# Device.net
KiCad netlist of a schematic drawn in Altium Designer
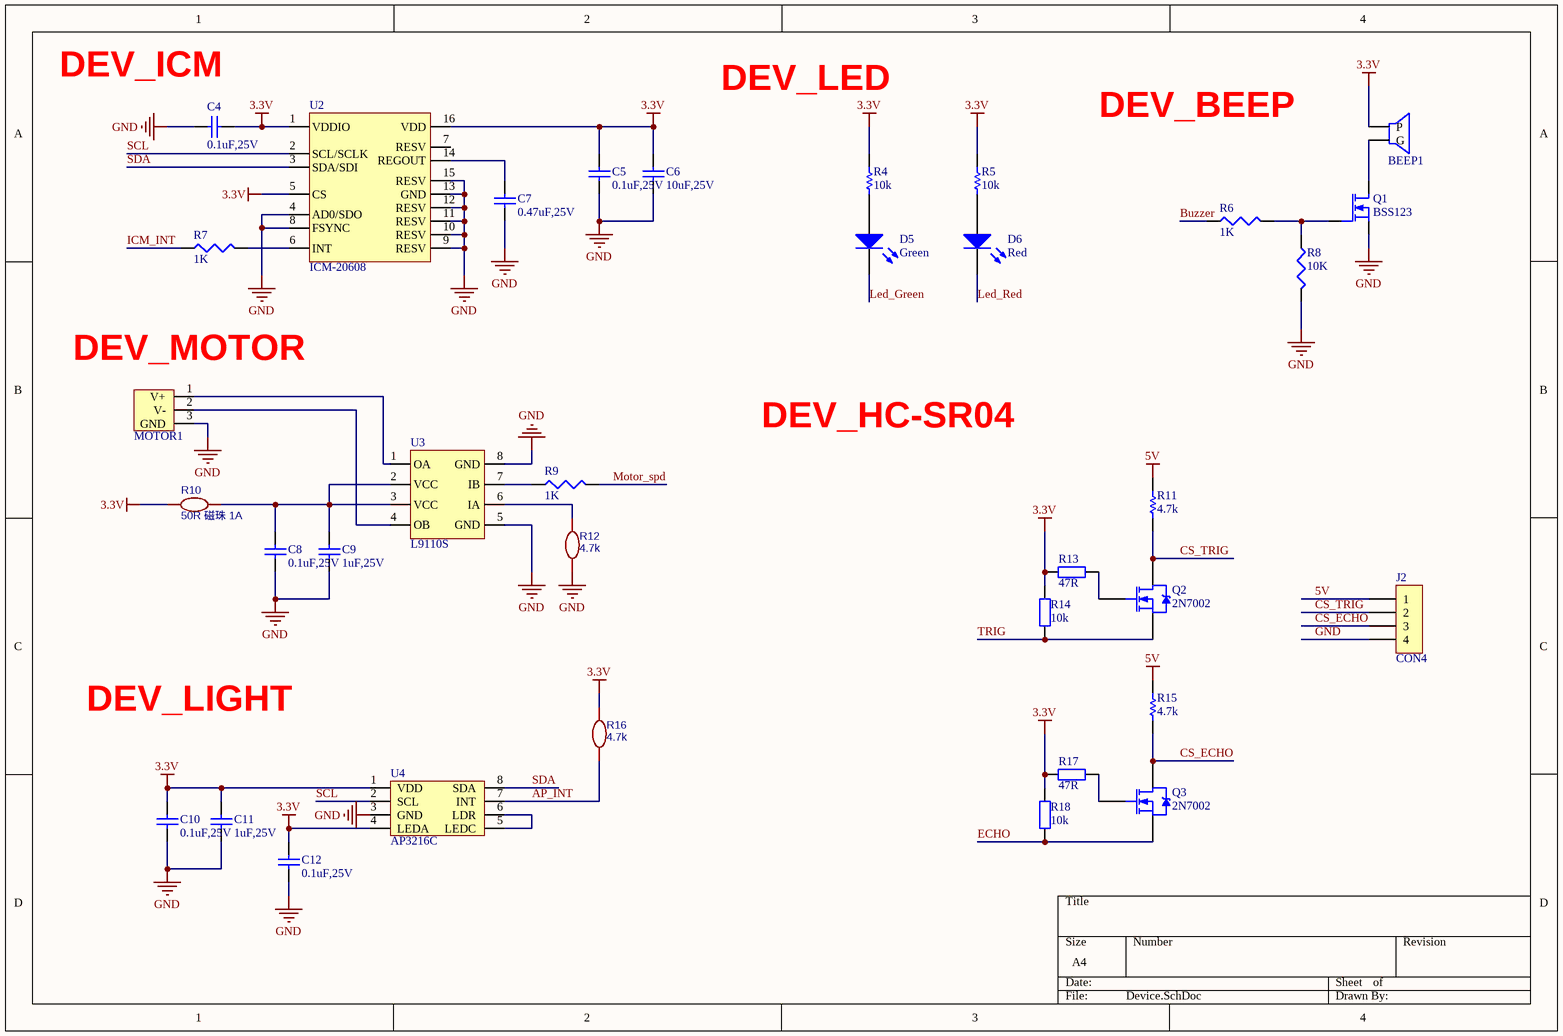
[diagram p0: Device.SchDoc]

(export (version "E")
  (design (tool "Eeschema 10.0.6"))
  (components
    (comp (ref "BEEP1")
      (value "BEEP")
      (footprint "BEEP")
      (description "3.3V有源蜂鸣器")
      (libsource (lib "Pandora_STM32L4_Board_V2.4") (part "BEEP"))
    )
    (comp (ref "C4")
      (value "0.1uF,25V")
      (footprint "0402_C")
      (description "贴片电容")
      (fields (field (name "PART NUMBER") "T_Cap_0603_0.1uF_25V_X5R") (field (name "TOLERANCE") "10%"))
      (libsource (lib "Database_Library") (part "Cap"))
    )
    (comp (ref "C5")
      (value "0.1uF,25V")
      (footprint "0402_C")
      (description "贴片电容")
      (fields (field (name "PART NUMBER") "T_Cap_0603_0.1uF_25V_X5R") (field (name "TOLERANCE") "10%"))
      (libsource (lib "Database_Library") (part "Cap"))
    )
    (comp (ref "C6")
      (value "10uF,25V")
      (footprint "0402_C")
      (description "贴片电容")
      (fields (field (name "PART NUMBER") "T_Cap_0603_0.1uF_25V_X5R") (field (name "TOLERANCE") "10%"))
      (libsource (lib "Database_Library") (part "Cap"))
    )
    (comp (ref "C7")
      (value "0.47uF,25V")
      (footprint "0402_C")
      (description "贴片电容")
      (fields (field (name "PART NUMBER") "T_Cap_0603_0.1uF_25V_X5R") (field (name "TOLERANCE") "10%"))
      (libsource (lib "Database_Library") (part "Cap"))
    )
    (comp (ref "C8")
      (value "0.1uF,25V")
      (footprint "0402_C")
      (description "贴片电容")
      (fields (field (name "PART NUMBER") "T_Cap_0603_0.1uF_25V_X5R") (field (name "TOLERANCE") "10%"))
      (libsource (lib "Database_Library") (part "Cap"))
    )
    (comp (ref "C9")
      (value "1uF,25V")
      (footprint "0402_C")
      (description "贴片电容")
      (fields (field (name "PART NUMBER") "T_Cap_0603_0.1uF_25V_X5R") (field (name "TOLERANCE") "10%"))
      (libsource (lib "Database_Library") (part "Cap"))
    )
    (comp (ref "C10")
      (value "0.1uF,25V")
      (footprint "0402_C")
      (description "贴片电容")
      (fields (field (name "PART NUMBER") "T_Cap_0603_0.1uF_25V_X5R") (field (name "TOLERANCE") "10%"))
      (libsource (lib "Database_Library") (part "Cap"))
    )
    (comp (ref "C11")
      (value "1uF,25V")
      (footprint "0402_C")
      (description "贴片电容")
      (fields (field (name "PART NUMBER") "T_Cap_0603_0.1uF_25V_X5R") (field (name "TOLERANCE") "10%"))
      (libsource (lib "Database_Library") (part "Cap"))
    )
    (comp (ref "C12")
      (value "0.1uF,25V")
      (footprint "0402_C")
      (description "贴片电容")
      (fields (field (name "PART NUMBER") "T_Cap_0603_0.1uF_25V_X5R") (field (name "TOLERANCE") "10%"))
      (libsource (lib "Database_Library") (part "Cap"))
    )
    (comp (ref "D5")
      (value "Green")
      (footprint "0603_LED")
      (description "红色LED灯")
      (fields (field (name "PART NUMBER") "T_LED_Red_0805"))
      (libsource (lib "Database_Library") (part "LED"))
    )
    (comp (ref "D6")
      (value "Red")
      (footprint "0603_LED")
      (description "红色LED灯")
      (fields (field (name "PART NUMBER") "T_LED_Red_0805"))
      (libsource (lib "Database_Library") (part "LED"))
    )
    (comp (ref "J2") (value "CON4") (description "Connector") (libsource (lib "Schlib1") (part "CON4")))
    (comp (ref "MOTOR1")
      (value "Motor-SMD")
      (footprint "MOTOR-SMD")
      (description "电机,SMD")
      (libsource (lib "Pandora_STM32L4_Board_V2.4") (part "Motor-SMD"))
    )
    (comp (ref "Q1")
      (value "BSS123")
      (footprint "SOT-23")
      (description "Mosfet, N-channel, Vds:100V, Id:0.15A, Vgs-th:2.8V, Rds-on:3.5ohm")
      (libsource (lib "HardWare_OF_BMS_V1.0") (part "BSS123"))
    )
    (comp (ref "Q2")
      (value "2N7002")
      (footprint "SOT-23!!!")
      (fields (field (name "PART NUMBER") "T_2N7002"))
      (libsource (lib "Database_Library") (part "NMOS"))
    )
    (comp (ref "Q3")
      (value "2N7002")
      (footprint "SOT-23!!!")
      (fields (field (name "PART NUMBER") "T_2N7002"))
      (libsource (lib "Database_Library") (part "NMOS"))
    )
    (comp (ref "R4")
      (value "10k")
      (footprint "0603_R")
      (description "贴片电阻")
      (fields (field (name "PART NUMBER") "T_Res_0603_10k_5%_1/10W") (field (name "POWER") "1/10W"))
      (libsource (lib "Database_Library") (part "Res_5%"))
    )
    (comp (ref "R5")
      (value "10k")
      (footprint "0603_R")
      (description "贴片电阻")
      (fields (field (name "PART NUMBER") "T_Res_0603_10k_5%_1/10W") (field (name "POWER") "1/10W"))
      (libsource (lib "Database_Library") (part "Res_5%"))
    )
    (comp (ref "R6")
      (value "1K")
      (footprint "0603_R")
      (description "Resistor, 1.5k, 0.1%, 0.0625W, 50V, 100PPM, 0402")
      (libsource (lib "AR_Resistors_SMD") (part "1.5k/0402/0063W/50V"))
    )
    (comp (ref "R7")
      (value "1K")
      (footprint "0603_R")
      (description "Resistor, 1.5k, 0.1%, 0.0625W, 50V, 100PPM, 0402")
      (libsource (lib "AR_Resistors_SMD") (part "1.5k/0402/0063W/50V"))
    )
    (comp (ref "R8")
      (value "10K")
      (footprint "0603_R")
      (description "Resistor, 1.5k, 0.1%, 0.0625W, 50V, 100PPM, 0402")
      (libsource (lib "AR_Resistors_SMD") (part "1.5k/0402/0063W/50V"))
    )
    (comp (ref "R9")
      (value "1K")
      (footprint "0603_R")
      (description "Resistor, 1.5k, 0.1%, 0.0625W, 50V, 100PPM, 0402")
      (libsource (lib "AR_Resistors_SMD") (part "1.5k/0402/0063W/50V"))
    )
    (comp (ref "R10")
      (value "50R 磁珠 1A")
      (footprint "0402_R")
      (fields (field (name "CONTRIBUTOR") "LCEDA_Lib"))
      (libsource (lib "altium-import") (part "root_2_100k_"))
    )
    (comp (ref "R11")
      (value "4.7k")
      (footprint "0603_R")
      (description "贴片电阻")
      (fields (field (name "PART NUMBER") "T_Res_0603_4.3k_5%_1/10W") (field (name "POWER") "1/10W"))
      (libsource (lib "Database_Library") (part "Res_5%"))
    )
    (comp (ref "R12")
      (value "4.7k")
      (footprint "0402_R")
      (fields (field (name "CONTRIBUTOR") "LCEDA_Lib"))
      (libsource (lib "altium-import") (part "root_3_100k_"))
    )
    (comp (ref "R13") (value "47R") (footprint "0603_R") (libsource (lib "MyLibrary") (part "Res")))
    (comp (ref "R14")
      (value "10k")
      (footprint "0603_R")
      (description "贴片电阻")
      (fields (field (name "PART NUMBER") "T_Res_0603_10k_1%_1/10W") (field (name "POWER") "1/10W"))
      (libsource (lib "Database_Library") (part "Res"))
    )
    (comp (ref "R15")
      (value "4.7k")
      (footprint "0603_R")
      (description "贴片电阻")
      (fields (field (name "PART NUMBER") "T_Res_0603_4.3k_5%_1/10W") (field (name "POWER") "1/10W"))
      (libsource (lib "Database_Library") (part "Res_5%"))
    )
    (comp (ref "R16")
      (value "4.7k")
      (footprint "0402_R")
      (fields (field (name "CONTRIBUTOR") "LCEDA_Lib"))
      (libsource (lib "altium-import") (part "root_3_100k_"))
    )
    (comp (ref "R17") (value "47R") (footprint "0603_R") (libsource (lib "MyLibrary") (part "Res")))
    (comp (ref "R18")
      (value "10k")
      (footprint "0603_R")
      (description "贴片电阻")
      (fields (field (name "PART NUMBER") "T_Res_0603_10k_1%_1/10W") (field (name "POWER") "1/10W"))
      (libsource (lib "Database_Library") (part "Res"))
    )
    (comp (ref "U2")
      (value "ICM-20608")
      (footprint "LGA-16-3*3*0.75")
      (description "三轴陀螺仪/三轴加速度计,")
      (libsource (lib "Pandora_STM32L4_Board_V2.4") (part "U-ICM-20608"))
    )
    (comp (ref "U3")
      (value "L9110S")
      (footprint "SOP-8")
      (description "电机驱动,800mA")
      (libsource (lib "Pandora_STM32L4_Board_V2.4") (part "U-L9110S"))
    )
    (comp (ref "U4")
      (value "AP3216C")
      (footprint "QFN-8-2.4*4.1")
      (description "Sensor.光照/距离")
      (libsource (lib "Pandora_STM32L4_Board_V2.4") (part "U-AP3216C"))
    )
  )
  (nets
    (net (code "1") (name "/AP_INT") (class "Default")
      (node (ref "R16") (pin "2") (pinfunction "2_2") (pintype "passive"))
      (node (ref "U4") (pin "7") (pinfunction "INT_7") (pintype "passive"))
    )
    (net (code "2") (name "/Buzzer") (class "Default")
      (node (ref "R6") (pin "1") (pinfunction "1_1") (pintype "passive"))
    )
    (net (code "3") (name "/CS_ECHO") (class "Default")
      (node (ref "J2") (pin "3") (pinfunction "3_3") (pintype "passive"))
      (node (ref "Q3") (pin "2") (pinfunction "D_2") (pintype "passive"))
      (node (ref "R15") (pin "1") (pinfunction "1_1") (pintype "passive"))
    )
    (net (code "4") (name "/CS_TRIG") (class "Default")
      (node (ref "J2") (pin "2") (pinfunction "2_2") (pintype "passive"))
      (node (ref "Q2") (pin "2") (pinfunction "D_2") (pintype "passive"))
      (node (ref "R11") (pin "1") (pinfunction "1_1") (pintype "passive"))
    )
    (net (code "5") (name "/ECHO") (class "Default")
      (node (ref "Q3") (pin "3") (pinfunction "S_3") (pintype "passive"))
      (node (ref "R18") (pin "1") (pinfunction "1_1") (pintype "passive"))
    )
    (net (code "6") (name "/ICM_INT") (class "Default")
      (node (ref "R7") (pin "1") (pinfunction "1_1") (pintype "passive"))
    )
    (net (code "7") (name "/Led_Green") (class "Default")
      (node (ref "D5") (pin "2") (pinfunction "K_2") (pintype "passive"))
    )
    (net (code "8") (name "/Led_Red") (class "Default")
      (node (ref "D6") (pin "2") (pinfunction "K_2") (pintype "passive"))
    )
    (net (code "9") (name "/Motor_spd") (class "Default")
      (node (ref "R9") (pin "2") (pinfunction "2_2") (pintype "passive"))
    )
    (net (code "10") (name "/SCL") (class "Default")
      (node (ref "U2") (pin "2") (pinfunction "SCL/SCLK_2") (pintype "passive"))
      (node (ref "U4") (pin "2") (pinfunction "SCL_2") (pintype "passive"))
    )
    (net (code "11") (name "/SDA") (class "Default")
      (node (ref "U2") (pin "3") (pinfunction "SDA/SDI_3") (pintype "passive"))
      (node (ref "U4") (pin "8") (pinfunction "SDA_8") (pintype "passive"))
    )
    (net (code "12") (name "/TRIG") (class "Default")
      (node (ref "Q2") (pin "3") (pinfunction "S_3") (pintype "passive"))
      (node (ref "R14") (pin "1") (pinfunction "1_1") (pintype "passive"))
    )
    (net (code "13") (name "3.3V") (class "Default")
      (node (ref "BEEP1") (pin "1") (pinfunction "P_1") (pintype "passive"))
      (node (ref "C10") (pin "1") (pinfunction "1_1") (pintype "passive"))
      (node (ref "C11") (pin "1") (pinfunction "1_1") (pintype "passive"))
      (node (ref "C12") (pin "1") (pinfunction "1_1") (pintype "passive"))
      (node (ref "C4") (pin "1") (pinfunction "1_1") (pintype "passive"))
      (node (ref "C5") (pin "1") (pinfunction "1_1") (pintype "passive"))
      (node (ref "C6") (pin "1") (pinfunction "1_1") (pintype "passive"))
      (node (ref "R10") (pin "2") (pinfunction "2_2") (pintype "passive"))
      (node (ref "R13") (pin "1") (pinfunction "1_1") (pintype "passive"))
      (node (ref "R14") (pin "2") (pinfunction "2_2") (pintype "passive"))
      (node (ref "R16") (pin "1") (pinfunction "1_1") (pintype "passive"))
      (node (ref "R17") (pin "1") (pinfunction "1_1") (pintype "passive"))
      (node (ref "R18") (pin "2") (pinfunction "2_2") (pintype "passive"))
      (node (ref "R4") (pin "2") (pinfunction "2_2") (pintype "passive"))
      (node (ref "R5") (pin "2") (pinfunction "2_2") (pintype "passive"))
      (node (ref "U2") (pin "1") (pinfunction "VDDIO_1") (pintype "passive"))
      (node (ref "U2") (pin "16") (pinfunction "VDD_16") (pintype "passive"))
      (node (ref "U2") (pin "5") (pinfunction "CS_5") (pintype "passive"))
      (node (ref "U4") (pin "1") (pinfunction "VDD_1") (pintype "passive"))
      (node (ref "U4") (pin "4") (pinfunction "LEDA_4") (pintype "passive"))
    )
    (net (code "14") (name "5V") (class "Default")
      (node (ref "J2") (pin "1") (pinfunction "1_1") (pintype "passive"))
      (node (ref "R11") (pin "2") (pinfunction "2_2") (pintype "passive"))
      (node (ref "R15") (pin "2") (pinfunction "2_2") (pintype "passive"))
    )
    (net (code "15") (name "GND") (class "Default")
      (node (ref "C10") (pin "2") (pinfunction "2_2") (pintype "passive"))
      (node (ref "C11") (pin "2") (pinfunction "2_2") (pintype "passive"))
      (node (ref "C12") (pin "2") (pinfunction "2_2") (pintype "passive"))
      (node (ref "C4") (pin "2") (pinfunction "2_2") (pintype "passive"))
      (node (ref "C5") (pin "2") (pinfunction "2_2") (pintype "passive"))
      (node (ref "C6") (pin "2") (pinfunction "2_2") (pintype "passive"))
      (node (ref "C7") (pin "2") (pinfunction "2_2") (pintype "passive"))
      (node (ref "C8") (pin "2") (pinfunction "2_2") (pintype "passive"))
      (node (ref "C9") (pin "2") (pinfunction "2_2") (pintype "passive"))
      (node (ref "J2") (pin "4") (pinfunction "4_4") (pintype "passive"))
      (node (ref "MOTOR1") (pin "3") (pinfunction "GND_3") (pintype "passive"))
      (node (ref "Q1") (pin "S") (pinfunction "2_S") (pintype "passive"))
      (node (ref "R12") (pin "2") (pinfunction "2_2") (pintype "passive"))
      (node (ref "R8") (pin "2") (pinfunction "2_2") (pintype "passive"))
      (node (ref "U2") (pin "10") (pinfunction "RESV_10") (pintype "passive"))
      (node (ref "U2") (pin "11") (pinfunction "RESV_11") (pintype "passive"))
      (node (ref "U2") (pin "12") (pinfunction "RESV_12") (pintype "passive"))
      (node (ref "U2") (pin "13") (pinfunction "GND_13") (pintype "passive"))
      (node (ref "U2") (pin "15") (pinfunction "RESV_15") (pintype "passive"))
      (node (ref "U2") (pin "4") (pinfunction "AD0/SDO_4") (pintype "passive"))
      (node (ref "U2") (pin "8") (pinfunction "FSYNC_8") (pintype "passive"))
      (node (ref "U2") (pin "9") (pinfunction "RESV_9") (pintype "passive"))
      (node (ref "U3") (pin "5") (pinfunction "GND_5") (pintype "passive"))
      (node (ref "U3") (pin "8") (pinfunction "GND_8") (pintype "passive"))
      (node (ref "U4") (pin "3") (pinfunction "GND_3") (pintype "passive"))
    )
    (net (code "16") (name "Net-(BEEP1-G)") (class "Default")
      (node (ref "BEEP1") (pin "2") (pinfunction "G_2") (pintype "passive"))
      (node (ref "Q1") (pin "D") (pinfunction "3_D") (pintype "passive"))
    )
    (net (code "17") (name "Net-(C8-Pad1)") (class "Default")
      (node (ref "C8") (pin "1") (pinfunction "1_1") (pintype "passive"))
      (node (ref "C9") (pin "1") (pinfunction "1_1") (pintype "passive"))
      (node (ref "R10") (pin "1") (pinfunction "1_1") (pintype "passive"))
      (node (ref "U3") (pin "2") (pinfunction "VCC_2") (pintype "passive"))
      (node (ref "U3") (pin "3") (pinfunction "VCC_3") (pintype "passive"))
    )
    (net (code "18") (name "Net-(D5-A)") (class "Default")
      (node (ref "D5") (pin "1") (pinfunction "A_1") (pintype "passive"))
      (node (ref "R4") (pin "1") (pinfunction "1_1") (pintype "passive"))
    )
    (net (code "19") (name "Net-(D6-A)") (class "Default")
      (node (ref "D6") (pin "1") (pinfunction "A_1") (pintype "passive"))
      (node (ref "R5") (pin "1") (pinfunction "1_1") (pintype "passive"))
    )
    (net (code "20") (name "Net-(MOTOR1-V+)") (class "Default")
      (node (ref "MOTOR1") (pin "1") (pinfunction "V+_1") (pintype "passive"))
      (node (ref "U3") (pin "1") (pinfunction "OA_1") (pintype "passive"))
    )
    (net (code "21") (name "Net-(MOTOR1-V-)") (class "Default")
      (node (ref "MOTOR1") (pin "2") (pinfunction "V-_2") (pintype "passive"))
      (node (ref "U3") (pin "4") (pinfunction "OB_4") (pintype "passive"))
    )
    (net (code "22") (name "Net-(Q1-1)") (class "Default")
      (node (ref "Q1") (pin "G") (pinfunction "1_G") (pintype "passive"))
      (node (ref "R6") (pin "2") (pinfunction "2_2") (pintype "passive"))
      (node (ref "R8") (pin "1") (pinfunction "1_1") (pintype "passive"))
    )
    (net (code "23") (name "Net-(Q2-G)") (class "Default")
      (node (ref "Q2") (pin "1") (pinfunction "G_1") (pintype "passive"))
      (node (ref "R13") (pin "2") (pinfunction "2_2") (pintype "passive"))
    )
    (net (code "24") (name "Net-(Q3-G)") (class "Default")
      (node (ref "Q3") (pin "1") (pinfunction "G_1") (pintype "passive"))
      (node (ref "R17") (pin "2") (pinfunction "2_2") (pintype "passive"))
    )
    (net (code "25") (name "Net-(U2-INT)") (class "Default")
      (node (ref "R7") (pin "2") (pinfunction "2_2") (pintype "passive"))
      (node (ref "U2") (pin "6") (pinfunction "INT_6") (pintype "passive"))
    )
    (net (code "26") (name "Net-(U2-REGOUT)") (class "Default")
      (node (ref "C7") (pin "1") (pinfunction "1_1") (pintype "passive"))
      (node (ref "U2") (pin "14") (pinfunction "REGOUT_14") (pintype "passive"))
    )
    (net (code "27") (name "Net-(U3-IA)") (class "Default")
      (node (ref "R12") (pin "1") (pinfunction "1_1") (pintype "passive"))
      (node (ref "U3") (pin "6") (pinfunction "IA_6") (pintype "passive"))
    )
    (net (code "28") (name "Net-(U3-IB)") (class "Default")
      (node (ref "R9") (pin "1") (pinfunction "1_1") (pintype "passive"))
      (node (ref "U3") (pin "7") (pinfunction "IB_7") (pintype "passive"))
    )
    (net (code "29") (name "Net-(U4-LDR)") (class "Default")
      (node (ref "U4") (pin "5") (pinfunction "LEDC_5") (pintype "passive"))
      (node (ref "U4") (pin "6") (pinfunction "LDR_6") (pintype "passive"))
    )
    (net (code "30") (name "unconnected-(U2-RESV-Pad7)") (class "Default")
      (node (ref "U2") (pin "7") (pinfunction "RESV_7") (pintype "passive"))
    )
  )
)
